# routeur_wemos_Maxi_v1_1c_2020-05-14_15-5.net
KiCad netlist of a schematic drawn in EasyEDA
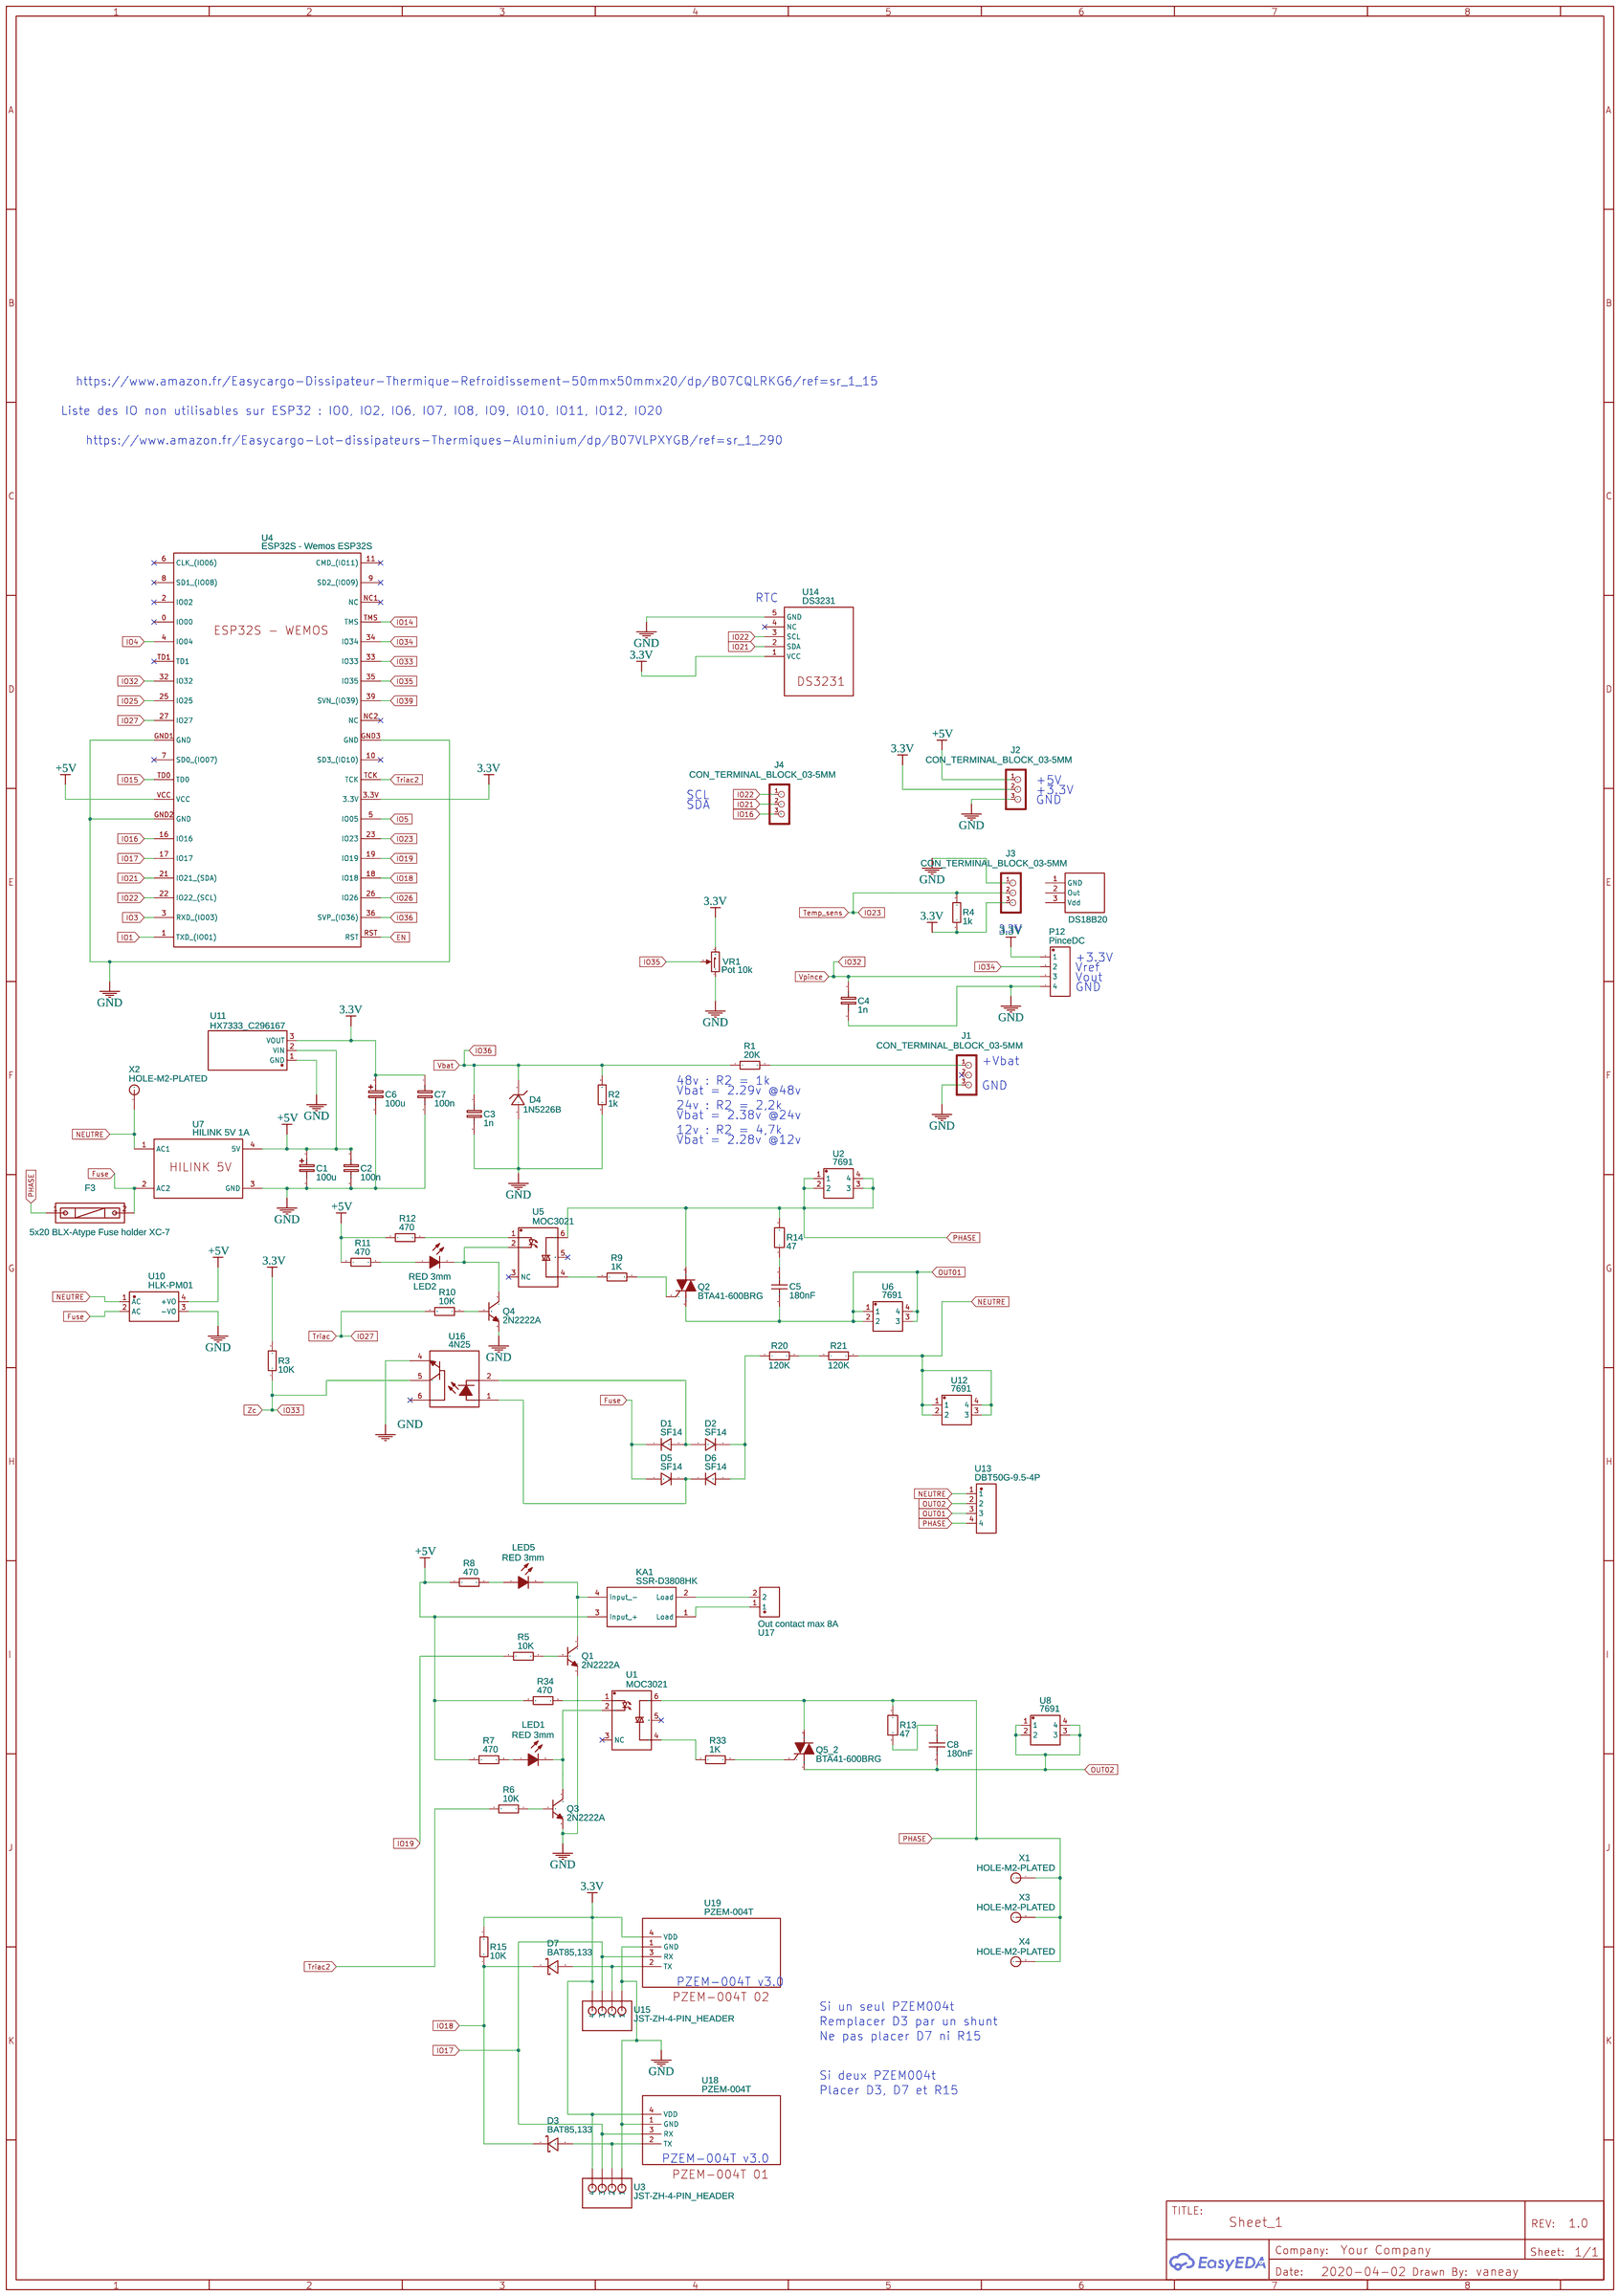
[diagram p0: schematic sheet]

(export (version "E")
  (design (tool "Eeschema 10.0.6"))
  (components
    (comp (ref "C1")
      (value "100u")
      (fields (field (name "BOM_Supplier Part") "C122609"))
      (libsource (lib "") (part "Cap_Electrolytic(TH)_D3.0XF1.5_EU"))
    )
    (comp (ref "C2")
      (value "100n")
      (fields (field (name "BOM_Supplier Part") "C94717"))
      (libsource (lib "") (part "Cap_RAD-0.1_EU_1"))
    )
    (comp (ref "C3")
      (value "1n")
      (fields (field (name "BOM_Supplier Part") "C192448"))
      (libsource (lib "") (part "Cap_RAD-0.1_EU_1"))
    )
    (comp (ref "C4")
      (value "1n")
      (fields (field (name "BOM_Supplier Part") "C192448"))
      (libsource (lib "") (part "Cap_RAD-0.1_EU"))
    )
    (comp (ref "C5")
      (value "180nF")
      (fields
        (field (name "BOM_Manufacturer Part") "SMXDX184KD2XXAB1515")
        (field (name "BOM_Supplier Part") "C155792")
      )
      (libsource (lib "") (part "SMXDX184KD2XXAB1515"))
    )
    (comp (ref "C6")
      (value "100u")
      (fields (field (name "BOM_Supplier Part") "C122609"))
      (libsource (lib "") (part "Cap_Electrolytic(TH)_D3.0XF1.5_EU"))
    )
    (comp (ref "C7")
      (value "100n")
      (fields (field (name "BOM_Supplier Part") "C94717"))
      (libsource (lib "") (part "Cap_RAD-0.1_EU_1"))
    )
    (comp (ref "C8")
      (value "180nF")
      (fields
        (field (name "BOM_Manufacturer Part") "SMXDX184KD2XXAB1515")
        (field (name "BOM_Supplier Part") "C155792")
      )
      (libsource (lib "") (part "SMXDX184KD2XXAB1515"))
    )
    (comp (ref "D1")
      (value "SF14")
      (fields (field (name "BOM_Supplier Part") "C331690"))
      (libsource (lib "") (part "SF14_1"))
    )
    (comp (ref "D2")
      (value "SF14")
      (fields (field (name "BOM_Supplier Part") "C331690"))
      (libsource (lib "") (part "SF14"))
    )
    (comp (ref "D3")
      (value "BAT85,133")
      (fields (field (name "BOM_Supplier Part") "C134301"))
      (libsource (lib "") (part "BAT85,133"))
    )
    (comp (ref "D4")
      (value "1N5226B")
      (fields (field (name "BOM_Supplier Part") "C51291"))
      (libsource (lib "") (part "1N751A"))
    )
    (comp (ref "D5")
      (value "SF14")
      (fields (field (name "BOM_Supplier Part") "C331690"))
      (libsource (lib "") (part "SF14"))
    )
    (comp (ref "D6")
      (value "SF14")
      (fields (field (name "BOM_Supplier Part") "C331690"))
      (libsource (lib "") (part "SF14_1"))
    )
    (comp (ref "D7")
      (value "BAT85,133")
      (fields (field (name "BOM_Supplier Part") "C134301"))
      (libsource (lib "") (part "BAT85,133"))
    )
    (comp (ref "F3")
      (value "5x20 BLX-Atype Fuse holder XC-7")
      (fields (field (name "BOM_Supplier Part") "C3131"))
      (libsource (lib "") (part "5x20 BLX-Atype Fuse holder XC-7"))
    )
    (comp (ref "J1")
      (value "CON_TERMINAL_BLOCK_03-5MM")
      (fields (field (name "BOM_Manufacturer Part") "?") (field (name "BOM_Supplier Part") "C182803"))
      (libsource (lib "") (part "Unknown_985_-425"))
    )
    (comp (ref "J2")
      (value "CON_TERMINAL_BLOCK_03-5MM")
      (fields (field (name "BOM_Manufacturer Part") "?") (field (name "BOM_Supplier Part") "C182803"))
      (libsource (lib "") (part "Unknown_1035_-715"))
    )
    (comp (ref "J3")
      (value "CON_TERMINAL_BLOCK_03-5MM")
      (fields (field (name "BOM_Manufacturer Part") "?") (field (name "BOM_Supplier Part") "C182803"))
      (libsource (lib "") (part "Unknown_1030_-610"))
    )
    (comp (ref "J4")
      (value "CON_TERMINAL_BLOCK_03-5MM")
      (fields (field (name "BOM_Manufacturer Part") "?") (field (name "BOM_Supplier Part") "C182803"))
      (libsource (lib "") (part "Unknown_795_-700"))
    )
    (comp (ref "KA1") (value "SSR-D3808HK") (libsource (lib "") (part "SSR-D3808HK")))
    (comp (ref "LED1")
      (value "RED 3mm")
      (fields
        (field (name "BOM_Manufacturer Part") "204-10SURD/S530-A3-L")
        (field (name "BOM_Supplier Part") "C99771")
      )
      (libsource (lib "") (part "204-10SURD/S530-A3-L"))
    )
    (comp (ref "LED2")
      (value "RED 3mm")
      (fields
        (field (name "BOM_Manufacturer Part") "204-10SURD/S530-A3-L")
        (field (name "BOM_Supplier Part") "C99771")
      )
      (libsource (lib "") (part "204-10SURD/S530-A3-L"))
    )
    (comp (ref "LED5")
      (value "RED 3mm")
      (fields
        (field (name "BOM_Manufacturer Part") "204-10SURD/S530-A3-L")
        (field (name "BOM_Supplier Part") "C99771")
      )
      (libsource (lib "") (part "204-10SURD/S530-A3-L"))
    )
    (comp (ref "P12")
      (value "PinceDC")
      (fields
        (field (name "BOM_Manufacturer Part") "EK508V-04P")
        (field (name "BOM_Supplier Part") "C182807")
      )
      (libsource (lib "") (part "WJ2EDGVC-5.08-4P"))
    )
    (comp (ref "Q1")
      (value "2N2222A")
      (fields (field (name "BOM_Supplier Part") "C358533"))
      (libsource (lib "") (part "2N2222A"))
    )
    (comp (ref "Q2")
      (value "BTA41-600BRG")
      (fields (field (name "BOM_Supplier Part") "C9103"))
      (libsource (lib "") (part "BTA41-600BRG_1"))
    )
    (comp (ref "Q3")
      (value "2N2222A")
      (fields (field (name "BOM_Supplier Part") "C358533"))
      (libsource (lib "") (part "2N2222A"))
    )
    (comp (ref "Q4")
      (value "2N2222A")
      (fields (field (name "BOM_Supplier Part") "C358533"))
      (libsource (lib "") (part "2N2222A"))
    )
    (comp (ref "Q5_2")
      (value "BTA41-600BRG")
      (fields (field (name "BOM_Supplier Part") "C9103"))
      (libsource (lib "") (part "BTA41-600BRG"))
    )
    (comp (ref "R1")
      (value "20K")
      (fields (field (name "BOM_Supplier Part") "C58592"))
      (libsource (lib "") (part "0805_1"))
    )
    (comp (ref "R2")
      (value "1k")
      (fields (field (name "BOM_Supplier Part") "C58592"))
      (libsource (lib "") (part "0805_2"))
    )
    (comp (ref "R3")
      (value "10K")
      (fields (field (name "BOM_Supplier Part") "C57436"))
      (libsource (lib "") (part "0805_2"))
    )
    (comp (ref "R4")
      (value "1k")
      (fields (field (name "BOM_Supplier Part") "C58592"))
      (libsource (lib "") (part "0805_2"))
    )
    (comp (ref "R5")
      (value "10K")
      (fields (field (name "BOM_Supplier Part") "C57436"))
      (libsource (lib "") (part "0805"))
    )
    (comp (ref "R6")
      (value "10K")
      (fields (field (name "BOM_Supplier Part") "C57436"))
      (libsource (lib "") (part "0805"))
    )
    (comp (ref "R7")
      (value "470")
      (fields (field (name "BOM_Supplier Part") "C58592"))
      (libsource (lib "") (part "0805_1"))
    )
    (comp (ref "R8")
      (value "470")
      (fields (field (name "BOM_Supplier Part") "C58592"))
      (libsource (lib "") (part "0805_1"))
    )
    (comp (ref "R9")
      (value "1K")
      (fields (field (name "BOM_Supplier Part") "C385291"))
      (libsource (lib "") (part "MFR1WSJT-52-5K1"))
    )
    (comp (ref "R10")
      (value "10K")
      (fields (field (name "BOM_Supplier Part") "C57436"))
      (libsource (lib "") (part "0805"))
    )
    (comp (ref "R11")
      (value "470")
      (fields (field (name "BOM_Supplier Part") "C58592"))
      (libsource (lib "") (part "0805_1"))
    )
    (comp (ref "R12")
      (value "470")
      (fields (field (name "BOM_Supplier Part") "C58592"))
      (libsource (lib "") (part "0805_1"))
    )
    (comp (ref "R13")
      (value "47")
      (fields
        (field (name "BOM_Manufacturer Part") "RN 2WS 47R F T/B A1")
        (field (name "BOM_Supplier Part") "C433590")
      )
      (libsource (lib "") (part "RN 2WS 47R F T/B A1"))
    )
    (comp (ref "R14")
      (value "47")
      (fields
        (field (name "BOM_Manufacturer Part") "RN 2WS 47R F T/B A1")
        (field (name "BOM_Supplier Part") "C433590")
      )
      (libsource (lib "") (part "RN 2WS 47R F T/B A1"))
    )
    (comp (ref "R15")
      (value "10K")
      (fields (field (name "BOM_Supplier Part") "C57436"))
      (libsource (lib "") (part "0805_2"))
    )
    (comp (ref "R20")
      (value "120K")
      (fields (field (name "BOM_Supplier Part") "C433673"))
      (libsource (lib "") (part "MFR1WSJT-52-5K1"))
    )
    (comp (ref "R21")
      (value "120K")
      (fields (field (name "BOM_Supplier Part") "C433673"))
      (libsource (lib "") (part "MFR1WSJT-52-5K1"))
    )
    (comp (ref "R33")
      (value "1K")
      (fields (field (name "BOM_Supplier Part") "C385291"))
      (libsource (lib "") (part "MFR1WSJT-52-5K1"))
    )
    (comp (ref "R34")
      (value "470")
      (fields (field (name "BOM_Supplier Part") "C58592"))
      (libsource (lib "") (part "0805_1"))
    )
    (comp (ref "U1")
      (value "MOC3021")
      (fields (field (name "BOM_Supplier Part") "C123202"))
      (libsource (lib "") (part "MOC3021"))
    )
    (comp (ref "U2")
      (value "7691")
      (fields (field (name "BOM_Supplier Part") "C238163"))
      (libsource (lib "") (part "7691"))
    )
    (comp (ref "U3")
      (value "JST-ZH-4-PIN_HEADER")
      (fields (field (name "BOM_Supplier Part") "C163034"))
      (libsource (lib "") (part "JST-ZH-4-PIN_HEADER"))
    )
    (comp (ref "U4")
      (value "ESP32S - Wemos ESP32S")
      (fields (field (name "BOM_Manufacturer Part") "ESP32S"))
      (libsource (lib "") (part "ESP32S - Wemos ESP32S"))
    )
    (comp (ref "U5")
      (value "MOC3021")
      (fields (field (name "BOM_Supplier Part") "C123202"))
      (libsource (lib "") (part "MOC3021_1"))
    )
    (comp (ref "U6")
      (value "7691")
      (fields (field (name "BOM_Supplier Part") "C238163"))
      (libsource (lib "") (part "7691"))
    )
    (comp (ref "U7")
      (value "HILINK 5V 1A")
      (fields (field (name "BOM_Manufacturer Part") "HLK-5M05") (field (name "BOM_Supplier Part") "C209907"))
      (libsource (lib "") (part "HILINK 5V corrected"))
    )
    (comp (ref "U8")
      (value "7691")
      (fields (field (name "BOM_Supplier Part") "C238163"))
      (libsource (lib "") (part "7691"))
    )
    (comp (ref "U9") (value "DS18B20") (libsource (lib "") (part "DS18B20")))
    (comp (ref "U10")
      (value "HLK-PM01")
      (fields (field (name "BOM_Supplier Part") "C209903"))
      (libsource (lib "") (part "HLK-PM01"))
    )
    (comp (ref "U11")
      (value "HX7333_C296167")
      (fields (field (name "BOM_Manufacturer Part") "HX7333") (field (name "BOM_Supplier Part") "C296167"))
      (libsource (lib "") (part "HX7333_C296167"))
    )
    (comp (ref "U12")
      (value "7691")
      (fields (field (name "BOM_Supplier Part") "C238163"))
      (libsource (lib "") (part "7691"))
    )
    (comp (ref "U13")
      (value "DBT50G-9.5-4P")
      (fields (field (name "BOM_Supplier Part") "C395960"))
      (libsource (lib "") (part "DBT50G-9.5-4P"))
    )
    (comp (ref "U14")
      (value "DS3231")
      (fields
        (field (name "BOM_Supplier Part") "https://www.amazon.fr/Delicacydex-dhorloge-arduino-Batterie-Raspberry/dp/B07P6RHHKX/ref=sr_1_2")
      )
      (libsource (lib "") (part "DS3231"))
    )
    (comp (ref "U15")
      (value "JST-ZH-4-PIN_HEADER")
      (fields (field (name "BOM_Supplier Part") "C163034"))
      (libsource (lib "") (part "JST-ZH-4-PIN_HEADER"))
    )
    (comp (ref "U16")
      (value "4N25")
      (fields (field (name "BOM_Supplier Part") "C115480"))
      (libsource (lib "") (part "4N25"))
    )
    (comp (ref "U17")
      (value "Out contact max 8A")
      (fields (field (name "BOM_Manufacturer Part") "282858-2") (field (name "BOM_Supplier Part") "C306150"))
      (libsource (lib "") (part "282858-2"))
    )
    (comp (ref "U18")
      (value "PZEM-004T")
      (fields (field (name "BOM_Manufacturer Part") "New SchematicLib"))
      (libsource (lib "") (part "PZEM-004T_1"))
    )
    (comp (ref "U19")
      (value "PZEM-004T")
      (fields (field (name "BOM_Manufacturer Part") "New SchematicLib"))
      (libsource (lib "") (part "PZEM-004T"))
    )
    (comp (ref "VR1") (value "Pot 10k") (libsource (lib "") (part "Pot")))
    (comp (ref "X1")
      (value "HOLE-M2-PLATED")
      (fields (field (name "BOM_Manufacturer Part") "New SchematicLib"))
      (libsource (lib "") (part "HOLE-M2-PLATED"))
    )
    (comp (ref "X2")
      (value "HOLE-M2-PLATED")
      (fields (field (name "BOM_Manufacturer Part") "New SchematicLib"))
      (libsource (lib "") (part "HOLE-M2-PLATED_1"))
    )
    (comp (ref "X3")
      (value "HOLE-M2-PLATED")
      (fields (field (name "BOM_Manufacturer Part") "New SchematicLib"))
      (libsource (lib "") (part "HOLE-M2-PLATED"))
    )
    (comp (ref "X4")
      (value "HOLE-M2-PLATED")
      (fields (field (name "BOM_Manufacturer Part") "New SchematicLib"))
      (libsource (lib "") (part "HOLE-M2-PLATED"))
    )
  )
  (nets
    (net (code "1") (name "+5V") (class "Default")
      (node (ref "C1") (pin "1") (pinfunction "1_1") (pintype "unspecified"))
      (node (ref "C2") (pin "1") (pinfunction "1_1") (pintype "unspecified"))
      (node (ref "J2") (pin "1") (pinfunction "1_1") (pintype "unspecified"))
      (node (ref "KA1") (pin "3") (pinfunction "Input_+_3") (pintype "unspecified"))
      (node (ref "R11") (pin "1") (pinfunction "1_1") (pintype "unspecified"))
      (node (ref "R12") (pin "1") (pinfunction "1_1") (pintype "unspecified"))
      (node (ref "R34") (pin "1") (pinfunction "1_1") (pintype "unspecified"))
      (node (ref "R7") (pin "1") (pinfunction "1_1") (pintype "unspecified"))
      (node (ref "R8") (pin "1") (pinfunction "1_1") (pintype "unspecified"))
      (node (ref "U10") (pin "4") (pinfunction "+VO_4") (pintype "unspecified"))
      (node (ref "U11") (pin "2") (pinfunction "VIN_2") (pintype "unspecified"))
      (node (ref "U4") (pin "VCC") (pinfunction "VCC_VCC") (pintype "unspecified"))
      (node (ref "U7") (pin "4") (pinfunction "5V_4") (pintype "unspecified"))
    )
    (net (code "2") (name "3.3V") (class "Default")
      (node (ref "C6") (pin "1") (pinfunction "1_1") (pintype "unspecified"))
      (node (ref "C7") (pin "1") (pinfunction "1_1") (pintype "unspecified"))
      (node (ref "J2") (pin "2") (pinfunction "2_2") (pintype "unspecified"))
      (node (ref "J3") (pin "3") (pinfunction "3_3") (pintype "unspecified"))
      (node (ref "P12") (pin "1") (pinfunction "1_1") (pintype "unspecified"))
      (node (ref "R15") (pin "2") (pinfunction "2_2") (pintype "unspecified"))
      (node (ref "R3") (pin "2") (pinfunction "2_2") (pintype "unspecified"))
      (node (ref "R4") (pin "1") (pinfunction "1_1") (pintype "unspecified"))
      (node (ref "U11") (pin "3") (pinfunction "VOUT_3") (pintype "unspecified"))
      (node (ref "U14") (pin "1") (pinfunction "VCC_1") (pintype "unspecified"))
      (node (ref "U15") (pin "P4") (pinfunction "4_P4") (pintype "unspecified"))
      (node (ref "U18") (pin "4") (pinfunction "VDD_4") (pintype "unspecified"))
      (node (ref "U19") (pin "4") (pinfunction "VDD_4") (pintype "unspecified"))
      (node (ref "U3") (pin "P4") (pinfunction "4_P4") (pintype "unspecified"))
      (node (ref "U4") (pin "3.3V") (pinfunction "3.3V_3.3V") (pintype "unspecified"))
      (node (ref "VR1") (pin "3") (pinfunction "3_3") (pintype "unspecified"))
    )
    (net (code "3") (name "EN") (class "Default")
      (node (ref "U4") (pin "RST") (pinfunction "RST_RST") (pintype "unspecified"))
    )
    (net (code "4") (name "Fuse") (class "Default")
      (node (ref "D1") (pin "1") (pinfunction "1_1") (pintype "unspecified"))
      (node (ref "D5") (pin "2") (pinfunction "2_2") (pintype "unspecified"))
      (node (ref "F3") (pin "2") (pinfunction "2_2") (pintype "unspecified"))
      (node (ref "U10") (pin "2") (pinfunction "AC_2") (pintype "unspecified"))
      (node (ref "U7") (pin "2") (pinfunction "AC2_2") (pintype "unspecified"))
    )
    (net (code "5") (name "GND") (class "Default")
      (node (ref "C1") (pin "2") (pinfunction "2_2") (pintype "unspecified"))
      (node (ref "C2") (pin "2") (pinfunction "2_2") (pintype "unspecified"))
      (node (ref "C3") (pin "2") (pinfunction "2_2") (pintype "unspecified"))
      (node (ref "C4") (pin "2") (pinfunction "2_2") (pintype "unspecified"))
      (node (ref "C6") (pin "2") (pinfunction "2_2") (pintype "unspecified"))
      (node (ref "C7") (pin "2") (pinfunction "2_2") (pintype "unspecified"))
      (node (ref "D4") (pin "2") (pinfunction "A_2") (pintype "unspecified"))
      (node (ref "J1") (pin "3") (pinfunction "3_3") (pintype "unspecified"))
      (node (ref "J2") (pin "3") (pinfunction "3_3") (pintype "unspecified"))
      (node (ref "J3") (pin "1") (pinfunction "1_1") (pintype "unspecified"))
      (node (ref "P12") (pin "4") (pinfunction "4_4") (pintype "unspecified"))
      (node (ref "Q1") (pin "3") (pinfunction "E_3") (pintype "unspecified"))
      (node (ref "Q3") (pin "3") (pinfunction "E_3") (pintype "unspecified"))
      (node (ref "Q4") (pin "3") (pinfunction "E_3") (pintype "unspecified"))
      (node (ref "R2") (pin "1") (pinfunction "1_1") (pintype "unspecified"))
      (node (ref "U10") (pin "3") (pinfunction "-VO_3") (pintype "unspecified"))
      (node (ref "U11") (pin "1") (pinfunction "GND_1") (pintype "unspecified"))
      (node (ref "U14") (pin "5") (pinfunction "GND_5") (pintype "unspecified"))
      (node (ref "U15") (pin "P1") (pinfunction "1_P1") (pintype "unspecified"))
      (node (ref "U16") (pin "4") (pinfunction "4_4") (pintype "unspecified"))
      (node (ref "U18") (pin "1") (pinfunction "GND_1") (pintype "unspecified"))
      (node (ref "U19") (pin "1") (pinfunction "GND_1") (pintype "unspecified"))
      (node (ref "U3") (pin "P1") (pinfunction "1_P1") (pintype "unspecified"))
      (node (ref "U4") (pin "GND1") (pinfunction "GND_GND1") (pintype "unspecified"))
      (node (ref "U4") (pin "GND2") (pinfunction "GND_GND2") (pintype "unspecified"))
      (node (ref "U4") (pin "GND3") (pinfunction "GND_GND3") (pintype "unspecified"))
      (node (ref "U7") (pin "3") (pinfunction "GND_3") (pintype "unspecified"))
      (node (ref "VR1") (pin "1") (pinfunction "1_1") (pintype "unspecified"))
    )
    (net (code "6") (name "IO1") (class "Default")
      (node (ref "U4") (pin "1") (pinfunction "TXD_(IO01)_1") (pintype "unspecified"))
    )
    (net (code "7") (name "IO3") (class "Default")
      (node (ref "U4") (pin "3") (pinfunction "RXD_(IO03)_3") (pintype "unspecified"))
    )
    (net (code "8") (name "IO4") (class "Default")
      (node (ref "U4") (pin "4") (pinfunction "IO04_4") (pintype "unspecified"))
    )
    (net (code "9") (name "IO5") (class "Default")
      (node (ref "U4") (pin "5") (pinfunction "IO05_5") (pintype "unspecified"))
    )
    (net (code "10") (name "IO14") (class "Default")
      (node (ref "U4") (pin "TMS") (pinfunction "TMS_TMS") (pintype "unspecified"))
    )
    (net (code "11") (name "IO15") (class "Default")
      (node (ref "U4") (pin "TD0") (pinfunction "TD0_TD0") (pintype "unspecified"))
    )
    (net (code "12") (name "IO16") (class "Default")
      (node (ref "J4") (pin "3") (pinfunction "3_3") (pintype "unspecified"))
      (node (ref "U4") (pin "16") (pinfunction "IO16_16") (pintype "unspecified"))
    )
    (net (code "13") (name "IO17") (class "Default")
      (node (ref "U15") (pin "P3") (pinfunction "3_P3") (pintype "unspecified"))
      (node (ref "U18") (pin "3") (pinfunction "RX_3") (pintype "unspecified"))
      (node (ref "U19") (pin "3") (pinfunction "RX_3") (pintype "unspecified"))
      (node (ref "U3") (pin "P3") (pinfunction "3_P3") (pintype "unspecified"))
      (node (ref "U4") (pin "17") (pinfunction "IO17_17") (pintype "unspecified"))
    )
    (net (code "14") (name "IO18") (class "Default")
      (node (ref "D3") (pin "1") (pinfunction "K_1") (pintype "unspecified"))
      (node (ref "D7") (pin "1") (pinfunction "K_1") (pintype "unspecified"))
      (node (ref "R15") (pin "1") (pinfunction "1_1") (pintype "unspecified"))
      (node (ref "U4") (pin "18") (pinfunction "IO18_18") (pintype "unspecified"))
    )
    (net (code "15") (name "IO19") (class "Default")
      (node (ref "R5") (pin "2") (pinfunction "2_2") (pintype "unspecified"))
      (node (ref "U4") (pin "19") (pinfunction "IO19_19") (pintype "unspecified"))
    )
    (net (code "16") (name "IO21") (class "Default")
      (node (ref "J4") (pin "2") (pinfunction "2_2") (pintype "unspecified"))
      (node (ref "U14") (pin "2") (pinfunction "SDA_2") (pintype "unspecified"))
      (node (ref "U4") (pin "21") (pinfunction "IO21_(SDA)_21") (pintype "unspecified"))
    )
    (net (code "17") (name "IO22") (class "Default")
      (node (ref "J4") (pin "1") (pinfunction "1_1") (pintype "unspecified"))
      (node (ref "U14") (pin "3") (pinfunction "SCL_3") (pintype "unspecified"))
      (node (ref "U4") (pin "22") (pinfunction "IO22_(SCL)_22") (pintype "unspecified"))
    )
    (net (code "18") (name "IO23") (class "Default")
      (node (ref "J3") (pin "2") (pinfunction "2_2") (pintype "unspecified"))
      (node (ref "R4") (pin "2") (pinfunction "2_2") (pintype "unspecified"))
      (node (ref "U4") (pin "23") (pinfunction "IO23_23") (pintype "unspecified"))
    )
    (net (code "19") (name "IO25") (class "Default")
      (node (ref "U4") (pin "25") (pinfunction "IO25_25") (pintype "unspecified"))
    )
    (net (code "20") (name "IO26") (class "Default")
      (node (ref "U4") (pin "26") (pinfunction "IO26_26") (pintype "unspecified"))
    )
    (net (code "21") (name "IO27") (class "Default")
      (node (ref "R10") (pin "2") (pinfunction "2_2") (pintype "unspecified"))
      (node (ref "U4") (pin "27") (pinfunction "IO27_27") (pintype "unspecified"))
    )
    (net (code "22") (name "IO32") (class "Default")
      (node (ref "C4") (pin "1") (pinfunction "1_1") (pintype "unspecified"))
      (node (ref "P12") (pin "3") (pinfunction "3_3") (pintype "unspecified"))
      (node (ref "U4") (pin "32") (pinfunction "IO32_32") (pintype "unspecified"))
    )
    (net (code "23") (name "IO33") (class "Default")
      (node (ref "R3") (pin "1") (pinfunction "1_1") (pintype "unspecified"))
      (node (ref "U16") (pin "5") (pinfunction "5_5") (pintype "unspecified"))
      (node (ref "U4") (pin "33") (pinfunction "IO33_33") (pintype "unspecified"))
    )
    (net (code "24") (name "IO34") (class "Default")
      (node (ref "P12") (pin "2") (pinfunction "2_2") (pintype "unspecified"))
      (node (ref "U4") (pin "34") (pinfunction "IO34_34") (pintype "unspecified"))
    )
    (net (code "25") (name "IO35") (class "Default")
      (node (ref "U4") (pin "35") (pinfunction "IO35_35") (pintype "unspecified"))
      (node (ref "VR1") (pin "2") (pinfunction "2_2") (pintype "unspecified"))
    )
    (net (code "26") (name "IO36") (class "Default")
      (node (ref "C3") (pin "1") (pinfunction "1_1") (pintype "unspecified"))
      (node (ref "D4") (pin "1") (pinfunction "C_1") (pintype "unspecified"))
      (node (ref "R1") (pin "1") (pinfunction "1_1") (pintype "unspecified"))
      (node (ref "R2") (pin "2") (pinfunction "2_2") (pintype "unspecified"))
      (node (ref "U4") (pin "36") (pinfunction "SVP_(IO36)_36") (pintype "unspecified"))
    )
    (net (code "27") (name "IO39") (class "Default")
      (node (ref "U4") (pin "39") (pinfunction "SVN_(IO39)_39") (pintype "unspecified"))
    )
    (net (code "28") (name "NEUTRE") (class "Default")
      (node (ref "R21") (pin "2") (pinfunction "2_2") (pintype "unspecified"))
      (node (ref "U10") (pin "1") (pinfunction "AC_1") (pintype "unspecified"))
      (node (ref "U12") (pin "1") (pinfunction "1_1") (pintype "unspecified"))
      (node (ref "U12") (pin "2") (pinfunction "2_2") (pintype "unspecified"))
      (node (ref "U12") (pin "3") (pinfunction "3_3") (pintype "unspecified"))
      (node (ref "U12") (pin "4") (pinfunction "4_4") (pintype "unspecified"))
      (node (ref "U13") (pin "1") (pinfunction "1_1") (pintype "unspecified"))
      (node (ref "U7") (pin "1") (pinfunction "AC1_1") (pintype "unspecified"))
      (node (ref "X2") (pin "1") (pinfunction "1_1") (pintype "unspecified"))
    )
    (net (code "29") (name "Net-(C5-Pad1)") (class "Default")
      (node (ref "C5") (pin "1") (pinfunction "1_1") (pintype "unspecified"))
      (node (ref "R14") (pin "1") (pinfunction "1_1") (pintype "unspecified"))
    )
    (net (code "30") (name "Net-(C8-Pad1)") (class "Default")
      (node (ref "C8") (pin "1") (pinfunction "1_1") (pintype "unspecified"))
      (node (ref "R13") (pin "1") (pinfunction "1_1") (pintype "unspecified"))
    )
    (net (code "31") (name "Net-(D1-Pad2)") (class "Default")
      (node (ref "D1") (pin "2") (pinfunction "2_2") (pintype "unspecified"))
      (node (ref "D2") (pin "2") (pinfunction "2_2") (pintype "unspecified"))
      (node (ref "U16") (pin "2") (pinfunction "2_2") (pintype "unspecified"))
    )
    (net (code "32") (name "Net-(D2-Pad1)") (class "Default")
      (node (ref "D2") (pin "1") (pinfunction "1_1") (pintype "unspecified"))
      (node (ref "D6") (pin "2") (pinfunction "2_2") (pintype "unspecified"))
      (node (ref "R20") (pin "1") (pinfunction "1_1") (pintype "unspecified"))
    )
    (net (code "33") (name "Net-(D3-A)") (class "Default")
      (node (ref "D3") (pin "2") (pinfunction "A_2") (pintype "unspecified"))
      (node (ref "U18") (pin "2") (pinfunction "TX_2") (pintype "unspecified"))
      (node (ref "U3") (pin "P2") (pinfunction "2_P2") (pintype "unspecified"))
    )
    (net (code "34") (name "Net-(D5-Pad1)") (class "Default")
      (node (ref "D5") (pin "1") (pinfunction "1_1") (pintype "unspecified"))
      (node (ref "D6") (pin "1") (pinfunction "1_1") (pintype "unspecified"))
      (node (ref "U16") (pin "1") (pinfunction "1_1") (pintype "unspecified"))
    )
    (net (code "35") (name "Net-(D7-A)") (class "Default")
      (node (ref "D7") (pin "2") (pinfunction "A_2") (pintype "unspecified"))
      (node (ref "U15") (pin "P2") (pinfunction "2_P2") (pintype "unspecified"))
      (node (ref "U19") (pin "2") (pinfunction "TX_2") (pintype "unspecified"))
    )
    (net (code "36") (name "Net-(J1-Pad1)") (class "Default")
      (node (ref "J1") (pin "1") (pinfunction "1_1") (pintype "unspecified"))
      (node (ref "R1") (pin "2") (pinfunction "2_2") (pintype "unspecified"))
    )
    (net (code "37") (name "Net-(KA1-Input_-)") (class "Default")
      (node (ref "KA1") (pin "4") (pinfunction "Input_-_4") (pintype "unspecified"))
      (node (ref "LED5") (pin "2") (pinfunction "K_2") (pintype "input"))
      (node (ref "Q1") (pin "1") (pinfunction "C_1") (pintype "unspecified"))
    )
    (net (code "38") (name "Net-(KA1-Load-Pad1)") (class "Default")
      (node (ref "KA1") (pin "1") (pinfunction "Load_1") (pintype "unspecified"))
      (node (ref "U17") (pin "1") (pinfunction "1_1") (pintype "unspecified"))
    )
    (net (code "39") (name "Net-(KA1-Load-Pad2)") (class "Default")
      (node (ref "KA1") (pin "2") (pinfunction "Load_2") (pintype "unspecified"))
      (node (ref "U17") (pin "2") (pinfunction "2_2") (pintype "unspecified"))
    )
    (net (code "40") (name "Net-(LED1-A)") (class "Default")
      (node (ref "LED1") (pin "1") (pinfunction "A_1") (pintype "input"))
      (node (ref "R7") (pin "2") (pinfunction "2_2") (pintype "unspecified"))
    )
    (net (code "41") (name "Net-(LED1-K)") (class "Default")
      (node (ref "LED1") (pin "2") (pinfunction "K_2") (pintype "input"))
      (node (ref "Q3") (pin "1") (pinfunction "C_1") (pintype "unspecified"))
      (node (ref "U1") (pin "2") (pinfunction "2_2") (pintype "unspecified"))
    )
    (net (code "42") (name "Net-(LED2-A)") (class "Default")
      (node (ref "LED2") (pin "1") (pinfunction "A_1") (pintype "input"))
      (node (ref "R11") (pin "2") (pinfunction "2_2") (pintype "unspecified"))
    )
    (net (code "43") (name "Net-(LED2-K)") (class "Default")
      (node (ref "LED2") (pin "2") (pinfunction "K_2") (pintype "input"))
      (node (ref "Q4") (pin "1") (pinfunction "C_1") (pintype "unspecified"))
      (node (ref "U5") (pin "2") (pinfunction "2_2") (pintype "unspecified"))
    )
    (net (code "44") (name "Net-(LED5-A)") (class "Default")
      (node (ref "LED5") (pin "1") (pinfunction "A_1") (pintype "input"))
      (node (ref "R8") (pin "2") (pinfunction "2_2") (pintype "unspecified"))
    )
    (net (code "45") (name "Net-(Q1-B)") (class "Default")
      (node (ref "Q1") (pin "2") (pinfunction "B_2") (pintype "unspecified"))
      (node (ref "R5") (pin "1") (pinfunction "1_1") (pintype "unspecified"))
    )
    (net (code "46") (name "Net-(Q2-G)") (class "Default")
      (node (ref "Q2") (pin "3") (pinfunction "G_3") (pintype "unspecified"))
      (node (ref "R9") (pin "2") (pinfunction "2_2") (pintype "unspecified"))
    )
    (net (code "47") (name "Net-(Q3-B)") (class "Default")
      (node (ref "Q3") (pin "2") (pinfunction "B_2") (pintype "unspecified"))
      (node (ref "R6") (pin "1") (pinfunction "1_1") (pintype "unspecified"))
    )
    (net (code "48") (name "Net-(Q4-B)") (class "Default")
      (node (ref "Q4") (pin "2") (pinfunction "B_2") (pintype "unspecified"))
      (node (ref "R10") (pin "1") (pinfunction "1_1") (pintype "unspecified"))
    )
    (net (code "49") (name "Net-(Q5_2-G)") (class "Default")
      (node (ref "Q5_2") (pin "3") (pinfunction "G_3") (pintype "unspecified"))
      (node (ref "R33") (pin "2") (pinfunction "2_2") (pintype "unspecified"))
    )
    (net (code "50") (name "Net-(R12-Pad2)") (class "Default")
      (node (ref "R12") (pin "2") (pinfunction "2_2") (pintype "unspecified"))
      (node (ref "U5") (pin "1") (pinfunction "1_1") (pintype "unspecified"))
    )
    (net (code "51") (name "Net-(R20-Pad2)") (class "Default")
      (node (ref "R20") (pin "2") (pinfunction "2_2") (pintype "unspecified"))
      (node (ref "R21") (pin "1") (pinfunction "1_1") (pintype "unspecified"))
    )
    (net (code "52") (name "Net-(R34-Pad2)") (class "Default")
      (node (ref "R34") (pin "2") (pinfunction "2_2") (pintype "unspecified"))
      (node (ref "U1") (pin "1") (pinfunction "1_1") (pintype "unspecified"))
    )
    (net (code "53") (name "Net-(U1-E)") (class "Default")
      (node (ref "R33") (pin "1") (pinfunction "1_1") (pintype "unspecified"))
      (node (ref "U1") (pin "4") (pinfunction "E_4") (pintype "unspecified"))
    )
    (net (code "54") (name "Net-(U5-E)") (class "Default")
      (node (ref "R9") (pin "1") (pinfunction "1_1") (pintype "unspecified"))
      (node (ref "U5") (pin "4") (pinfunction "E_4") (pintype "unspecified"))
    )
    (net (code "55") (name "OUT01") (class "Default")
      (node (ref "C5") (pin "2") (pinfunction "2_2") (pintype "unspecified"))
      (node (ref "Q2") (pin "1") (pinfunction "M1_1") (pintype "unspecified"))
      (node (ref "U13") (pin "3") (pinfunction "3_3") (pintype "unspecified"))
      (node (ref "U6") (pin "1") (pinfunction "1_1") (pintype "unspecified"))
      (node (ref "U6") (pin "2") (pinfunction "2_2") (pintype "unspecified"))
      (node (ref "U6") (pin "3") (pinfunction "3_3") (pintype "unspecified"))
      (node (ref "U6") (pin "4") (pinfunction "4_4") (pintype "unspecified"))
    )
    (net (code "56") (name "OUT02") (class "Default")
      (node (ref "C8") (pin "2") (pinfunction "2_2") (pintype "unspecified"))
      (node (ref "Q5_2") (pin "1") (pinfunction "M1_1") (pintype "unspecified"))
      (node (ref "U13") (pin "2") (pinfunction "2_2") (pintype "unspecified"))
      (node (ref "U8") (pin "1") (pinfunction "1_1") (pintype "unspecified"))
      (node (ref "U8") (pin "2") (pinfunction "2_2") (pintype "unspecified"))
      (node (ref "U8") (pin "3") (pinfunction "3_3") (pintype "unspecified"))
      (node (ref "U8") (pin "4") (pinfunction "4_4") (pintype "unspecified"))
    )
    (net (code "57") (name "PHASE") (class "Default")
      (node (ref "F3") (pin "1") (pinfunction "1_1") (pintype "unspecified"))
      (node (ref "Q2") (pin "2") (pinfunction "M2_2") (pintype "unspecified"))
      (node (ref "Q5_2") (pin "2") (pinfunction "M2_2") (pintype "unspecified"))
      (node (ref "R13") (pin "2") (pinfunction "2_2") (pintype "unspecified"))
      (node (ref "R14") (pin "2") (pinfunction "2_2") (pintype "unspecified"))
      (node (ref "U1") (pin "6") (pinfunction "BASE_6") (pintype "unspecified"))
      (node (ref "U13") (pin "4") (pinfunction "4_4") (pintype "unspecified"))
      (node (ref "U2") (pin "1") (pinfunction "1_1") (pintype "unspecified"))
      (node (ref "U2") (pin "2") (pinfunction "2_2") (pintype "unspecified"))
      (node (ref "U2") (pin "3") (pinfunction "3_3") (pintype "unspecified"))
      (node (ref "U2") (pin "4") (pinfunction "4_4") (pintype "unspecified"))
      (node (ref "U5") (pin "6") (pinfunction "BASE_6") (pintype "unspecified"))
      (node (ref "X1") (pin "1") (pinfunction "1_1") (pintype "unspecified"))
      (node (ref "X3") (pin "1") (pinfunction "1_1") (pintype "unspecified"))
      (node (ref "X4") (pin "1") (pinfunction "1_1") (pintype "unspecified"))
    )
    (net (code "58") (name "Triac2") (class "Default")
      (node (ref "R6") (pin "2") (pinfunction "2_2") (pintype "unspecified"))
      (node (ref "U4") (pin "TCK") (pinfunction "TCK_TCK") (pintype "unspecified"))
    )
    (net (code "59") (name "unconnected-(J1-Pad2)") (class "Default")
      (node (ref "J1") (pin "2") (pinfunction "2_2") (pintype "unspecified+no_connect"))
    )
    (net (code "60") (name "unconnected-(U1-NC-Pad3)") (class "Default")
      (node (ref "U1") (pin "3") (pinfunction "NC_3") (pintype "unspecified+no_connect"))
    )
    (net (code "61") (name "unconnected-(U1-SUB-Pad5)") (class "Default")
      (node (ref "U1") (pin "5") (pinfunction "SUB_5") (pintype "unspecified+no_connect"))
    )
    (net (code "62") (name "unconnected-(U4-CLK_(IO06)-Pad6)") (class "Default")
      (node (ref "U4") (pin "6") (pinfunction "CLK_(IO06)_6") (pintype "unspecified+no_connect"))
    )
    (net (code "63") (name "unconnected-(U4-CMD_(IO11)-Pad11)") (class "Default")
      (node (ref "U4") (pin "11") (pinfunction "CMD_(IO11)_11") (pintype "unspecified+no_connect"))
    )
    (net (code "64") (name "unconnected-(U4-IO00-Pad0)") (class "Default")
      (node (ref "U4") (pin "0") (pinfunction "IO00_0") (pintype "unspecified+no_connect"))
    )
    (net (code "65") (name "unconnected-(U4-IO02-Pad2)") (class "Default")
      (node (ref "U4") (pin "2") (pinfunction "IO02_2") (pintype "unspecified+no_connect"))
    )
    (net (code "66") (name "unconnected-(U4-NC-PadNC1)") (class "Default")
      (node (ref "U4") (pin "NC1") (pinfunction "NC_NC1") (pintype "unspecified+no_connect"))
    )
    (net (code "67") (name "unconnected-(U4-NC-PadNC2)") (class "Default")
      (node (ref "U4") (pin "NC2") (pinfunction "NC_NC2") (pintype "unspecified+no_connect"))
    )
    (net (code "68") (name "unconnected-(U4-PadTD1)") (class "Default")
      (node (ref "U4") (pin "TD1") (pinfunction "TD1_TD1") (pintype "unspecified+no_connect"))
    )
    (net (code "69") (name "unconnected-(U4-SD0_(IO07)-Pad7)") (class "Default")
      (node (ref "U4") (pin "7") (pinfunction "SD0_(IO07)_7") (pintype "unspecified+no_connect"))
    )
    (net (code "70") (name "unconnected-(U4-SD1_(IO08)-Pad8)") (class "Default")
      (node (ref "U4") (pin "8") (pinfunction "SD1_(IO08)_8") (pintype "unspecified+no_connect"))
    )
    (net (code "71") (name "unconnected-(U4-SD2_(IO09)-Pad9)") (class "Default")
      (node (ref "U4") (pin "9") (pinfunction "SD2_(IO09)_9") (pintype "unspecified+no_connect"))
    )
    (net (code "72") (name "unconnected-(U4-SD3_(IO10)-Pad10)") (class "Default")
      (node (ref "U4") (pin "10") (pinfunction "SD3_(IO10)_10") (pintype "unspecified+no_connect"))
    )
    (net (code "73") (name "unconnected-(U5-NC-Pad3)") (class "Default")
      (node (ref "U5") (pin "3") (pinfunction "NC_3") (pintype "unspecified+no_connect"))
    )
    (net (code "74") (name "unconnected-(U5-SUB-Pad5)") (class "Default")
      (node (ref "U5") (pin "5") (pinfunction "SUB_5") (pintype "unspecified+no_connect"))
    )
    (net (code "75") (name "unconnected-(U9-GND-Pad1)") (class "Default")
      (node (ref "U9") (pin "1") (pinfunction "GND_1") (pintype "unspecified"))
    )
    (net (code "76") (name "unconnected-(U9-Out-Pad2)") (class "Default")
      (node (ref "U9") (pin "2") (pinfunction "Out_2") (pintype "unspecified"))
    )
    (net (code "77") (name "unconnected-(U9-Vdd-Pad3)") (class "Default")
      (node (ref "U9") (pin "3") (pinfunction "Vdd_3") (pintype "unspecified"))
    )
    (net (code "78") (name "unconnected-(U14-NC-Pad4)") (class "Default")
      (node (ref "U14") (pin "4") (pinfunction "NC_4") (pintype "unspecified+no_connect"))
    )
    (net (code "79") (name "unconnected-(U16-Pad6)") (class "Default")
      (node (ref "U16") (pin "6") (pinfunction "6_6") (pintype "unspecified+no_connect"))
    )
  )
)
